# QuadPortIEC.net
KiCad netlist of a schematic drawn in EAGLE
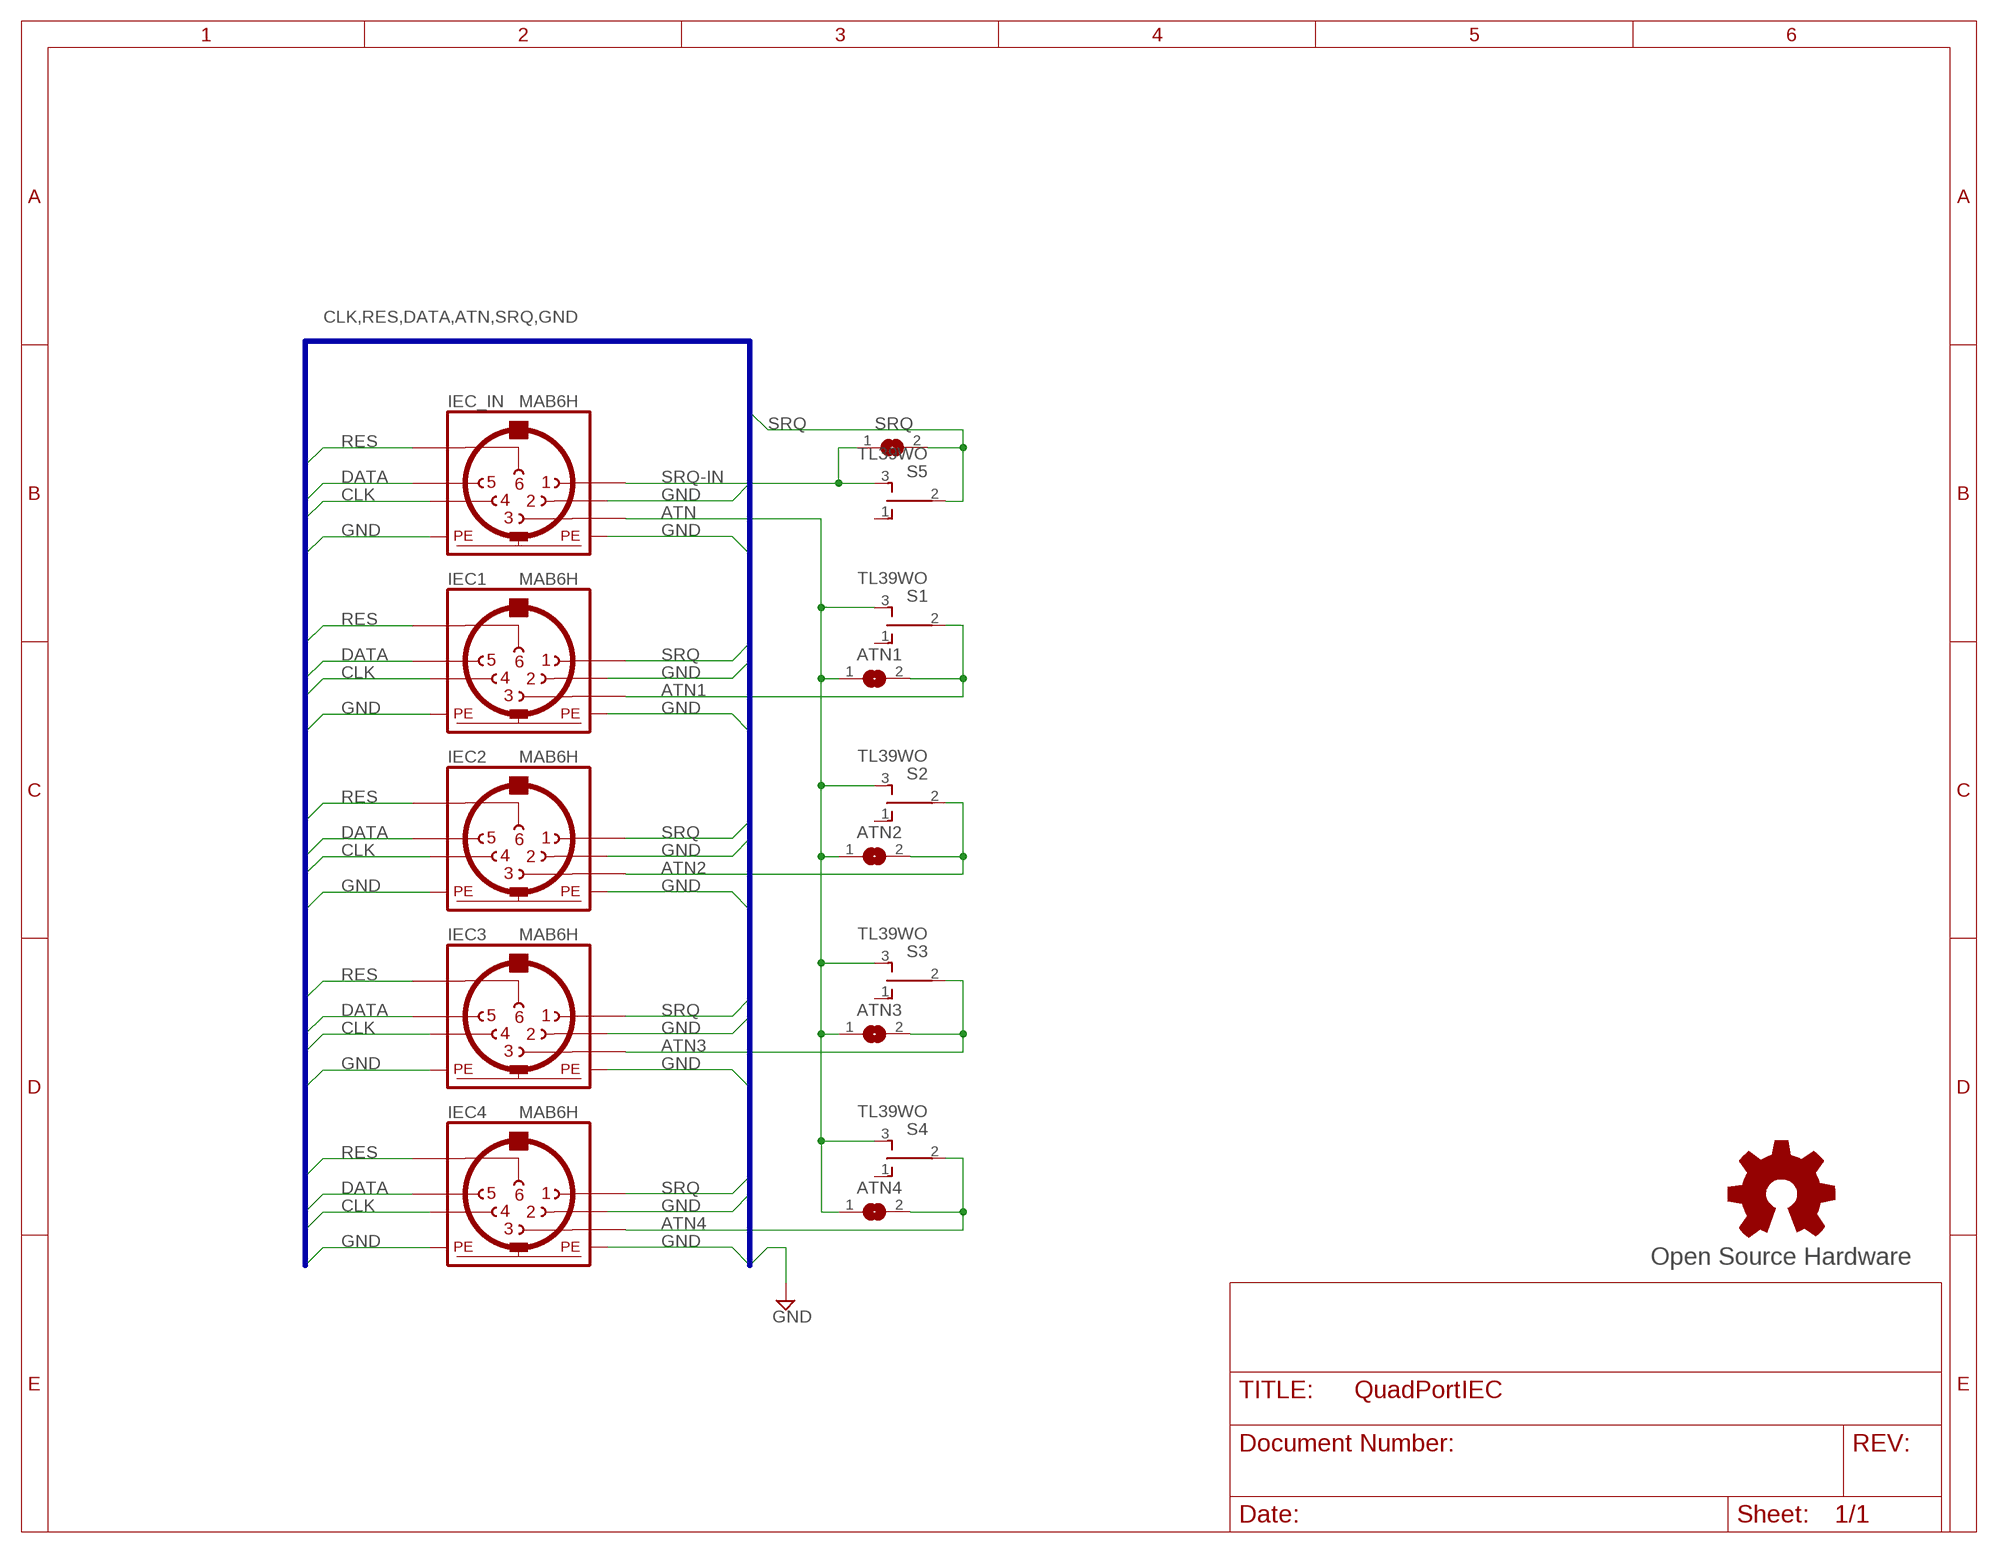
[diagram p0: schematic, sheet 1]

(export (version "E")
  (design (tool "Eeschema 10.0.6"))
  (components
    (comp (ref "ATN1")
      (value "SJ")
      (footprint "eagle-import:SJ")
      (libsource (lib "eagle-import") (part "SJ"))
    )
    (comp (ref "ATN2")
      (value "SJ")
      (footprint "eagle-import:SJ")
      (libsource (lib "eagle-import") (part "SJ"))
    )
    (comp (ref "ATN3")
      (value "SJ")
      (footprint "eagle-import:SJ")
      (libsource (lib "eagle-import") (part "SJ"))
    )
    (comp (ref "ATN4")
      (value "SJ")
      (footprint "eagle-import:SJ")
      (libsource (lib "eagle-import") (part "SJ"))
    )
    (comp (ref "GOLD_ORB_SM1")
      (value "Open Source Hardware")
      (footprint "eagle-import:OSHW_8MM")
      (libsource (lib "eagle-import") (part "OSHWLOGOLOGO8MM"))
    )
    (comp (ref "IEC1")
      (value "MAB6H")
      (footprint "eagle-import:MAB6H")
      (libsource (lib "eagle-import") (part "MAB6H"))
    )
    (comp (ref "IEC2")
      (value "MAB6H")
      (footprint "eagle-import:MAB6H")
      (libsource (lib "eagle-import") (part "MAB6H"))
    )
    (comp (ref "IEC3")
      (value "MAB6H")
      (footprint "eagle-import:MAB6H")
      (libsource (lib "eagle-import") (part "MAB6H"))
    )
    (comp (ref "IEC4")
      (value "MAB6H")
      (footprint "eagle-import:MAB6H")
      (libsource (lib "eagle-import") (part "MAB6H"))
    )
    (comp (ref "IEC_IN")
      (value "MAB6H")
      (footprint "eagle-import:MAB6H")
      (libsource (lib "eagle-import") (part "MAB6H"))
    )
    (comp (ref "S1")
      (value "TL39WO")
      (footprint "eagle-import:TL3XWO")
      (libsource (lib "eagle-import") (part "TL39WO"))
    )
    (comp (ref "S2")
      (value "TL39WO")
      (footprint "eagle-import:TL3XWO")
      (libsource (lib "eagle-import") (part "TL39WO"))
    )
    (comp (ref "S3")
      (value "TL39WO")
      (footprint "eagle-import:TL3XWO")
      (libsource (lib "eagle-import") (part "TL39WO"))
    )
    (comp (ref "S4")
      (value "TL39WO")
      (footprint "eagle-import:TL3XWO")
      (libsource (lib "eagle-import") (part "TL39WO"))
    )
    (comp (ref "S5")
      (value "TL39WO")
      (footprint "eagle-import:TL3XWO")
      (libsource (lib "eagle-import") (part "TL39WO"))
    )
    (comp (ref "SRQ") (value "SJ") (footprint "eagle-import:SJ") (libsource (lib "eagle-import") (part "SJ")))
  )
  (nets
    (net (code "1") (name "/ATN") (class "Default")
      (node (ref "ATN1") (pin "1") (pinfunction "1_1") (pintype "passive"))
      (node (ref "ATN2") (pin "1") (pinfunction "1_1") (pintype "passive"))
      (node (ref "ATN3") (pin "1") (pinfunction "1_1") (pintype "passive"))
      (node (ref "ATN4") (pin "1") (pinfunction "1_1") (pintype "passive"))
      (node (ref "IEC_IN") (pin "3") (pinfunction "3_3") (pintype "passive"))
      (node (ref "S1") (pin "3") (pinfunction "S_3") (pintype "passive"))
      (node (ref "S2") (pin "3") (pinfunction "S_3") (pintype "passive"))
      (node (ref "S3") (pin "3") (pinfunction "S_3") (pintype "passive"))
      (node (ref "S4") (pin "3") (pinfunction "S_3") (pintype "passive"))
    )
    (net (code "2") (name "/ATN1") (class "Default")
      (node (ref "ATN1") (pin "2") (pinfunction "2_2") (pintype "passive"))
      (node (ref "IEC1") (pin "3") (pinfunction "3_3") (pintype "passive"))
      (node (ref "S1") (pin "2") (pinfunction "P_2") (pintype "passive"))
    )
    (net (code "3") (name "/ATN2") (class "Default")
      (node (ref "ATN2") (pin "2") (pinfunction "2_2") (pintype "passive"))
      (node (ref "IEC2") (pin "3") (pinfunction "3_3") (pintype "passive"))
      (node (ref "S2") (pin "2") (pinfunction "P_2") (pintype "passive"))
    )
    (net (code "4") (name "/ATN3") (class "Default")
      (node (ref "ATN3") (pin "2") (pinfunction "2_2") (pintype "passive"))
      (node (ref "IEC3") (pin "3") (pinfunction "3_3") (pintype "passive"))
      (node (ref "S3") (pin "2") (pinfunction "P_2") (pintype "passive"))
    )
    (net (code "5") (name "/ATN4") (class "Default")
      (node (ref "ATN4") (pin "2") (pinfunction "2_2") (pintype "passive"))
      (node (ref "IEC4") (pin "3") (pinfunction "3_3") (pintype "passive"))
      (node (ref "S4") (pin "2") (pinfunction "P_2") (pintype "passive"))
    )
    (net (code "6") (name "/CLK") (class "Default")
      (node (ref "IEC1") (pin "4") (pinfunction "4_4") (pintype "passive"))
      (node (ref "IEC2") (pin "4") (pinfunction "4_4") (pintype "passive"))
      (node (ref "IEC3") (pin "4") (pinfunction "4_4") (pintype "passive"))
      (node (ref "IEC4") (pin "4") (pinfunction "4_4") (pintype "passive"))
      (node (ref "IEC_IN") (pin "4") (pinfunction "4_4") (pintype "passive"))
    )
    (net (code "7") (name "/DATA") (class "Default")
      (node (ref "IEC1") (pin "5") (pinfunction "5_5") (pintype "passive"))
      (node (ref "IEC2") (pin "5") (pinfunction "5_5") (pintype "passive"))
      (node (ref "IEC3") (pin "5") (pinfunction "5_5") (pintype "passive"))
      (node (ref "IEC4") (pin "5") (pinfunction "5_5") (pintype "passive"))
      (node (ref "IEC_IN") (pin "5") (pinfunction "5_5") (pintype "passive"))
    )
    (net (code "8") (name "/RES") (class "Default")
      (node (ref "IEC1") (pin "6") (pinfunction "6_6") (pintype "passive"))
      (node (ref "IEC2") (pin "6") (pinfunction "6_6") (pintype "passive"))
      (node (ref "IEC3") (pin "6") (pinfunction "6_6") (pintype "passive"))
      (node (ref "IEC4") (pin "6") (pinfunction "6_6") (pintype "passive"))
      (node (ref "IEC_IN") (pin "6") (pinfunction "6_6") (pintype "passive"))
    )
    (net (code "9") (name "/SRQ") (class "Default")
      (node (ref "IEC1") (pin "1") (pinfunction "1_1") (pintype "passive"))
      (node (ref "IEC2") (pin "1") (pinfunction "1_1") (pintype "passive"))
      (node (ref "IEC3") (pin "1") (pinfunction "1_1") (pintype "passive"))
      (node (ref "IEC4") (pin "1") (pinfunction "1_1") (pintype "passive"))
      (node (ref "S5") (pin "2") (pinfunction "P_2") (pintype "passive"))
      (node (ref "SRQ") (pin "2") (pinfunction "2_2") (pintype "passive"))
    )
    (net (code "10") (name "/SRQ-IN") (class "Default")
      (node (ref "IEC_IN") (pin "1") (pinfunction "1_1") (pintype "passive"))
      (node (ref "S5") (pin "3") (pinfunction "S_3") (pintype "passive"))
      (node (ref "SRQ") (pin "1") (pinfunction "1_1") (pintype "passive"))
    )
    (net (code "12") (name "GND") (class "Default")
      (node (ref "IEC1") (pin "2") (pinfunction "2_2") (pintype "passive"))
      (node (ref "IEC1") (pin "PE") (pinfunction "PE_PE") (pintype "power_in"))
      (node (ref "IEC1") (pin "PE@") (pinfunction "PE_PE@") (pintype "power_in"))
      (node (ref "IEC2") (pin "2") (pinfunction "2_2") (pintype "passive"))
      (node (ref "IEC2") (pin "PE") (pinfunction "PE_PE") (pintype "power_in"))
      (node (ref "IEC2") (pin "PE@") (pinfunction "PE_PE@") (pintype "power_in"))
      (node (ref "IEC3") (pin "2") (pinfunction "2_2") (pintype "passive"))
      (node (ref "IEC3") (pin "PE") (pinfunction "PE_PE") (pintype "power_in"))
      (node (ref "IEC3") (pin "PE@") (pinfunction "PE_PE@") (pintype "power_in"))
      (node (ref "IEC4") (pin "2") (pinfunction "2_2") (pintype "passive"))
      (node (ref "IEC4") (pin "PE") (pinfunction "PE_PE") (pintype "power_in"))
      (node (ref "IEC4") (pin "PE@") (pinfunction "PE_PE@") (pintype "power_in"))
      (node (ref "IEC_IN") (pin "2") (pinfunction "2_2") (pintype "passive"))
      (node (ref "IEC_IN") (pin "PE") (pinfunction "PE_PE") (pintype "power_in"))
      (node (ref "IEC_IN") (pin "PE@") (pinfunction "PE_PE@") (pintype "power_in"))
    )
    (net (code "13") (name "unconnected-(S1-O-Pad1)") (class "Default")
      (node (ref "S1") (pin "1") (pinfunction "O_1") (pintype "passive"))
    )
    (net (code "14") (name "unconnected-(S2-O-Pad1)") (class "Default")
      (node (ref "S2") (pin "1") (pinfunction "O_1") (pintype "passive"))
    )
    (net (code "15") (name "unconnected-(S3-O-Pad1)") (class "Default")
      (node (ref "S3") (pin "1") (pinfunction "O_1") (pintype "passive"))
    )
    (net (code "16") (name "unconnected-(S4-O-Pad1)") (class "Default")
      (node (ref "S4") (pin "1") (pinfunction "O_1") (pintype "passive"))
    )
    (net (code "17") (name "unconnected-(S5-O-Pad1)") (class "Default")
      (node (ref "S5") (pin "1") (pinfunction "O_1") (pintype "passive"))
    )
  )
)
